# HighPowerWS2801_v1_smd.net
KiCad netlist of a schematic drawn in EAGLE
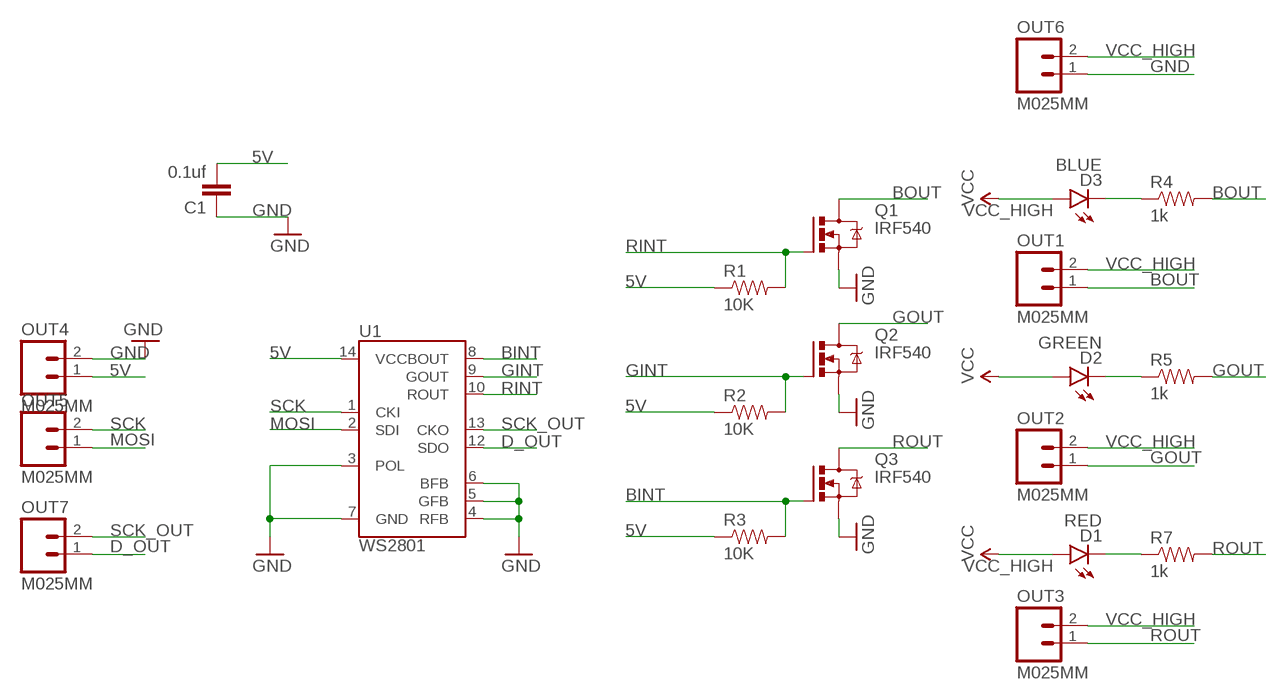
[diagram p0: schematic, sheet 1]

(export (version "E")
  (design (tool "Eeschema 10.0.6"))
  (components
    (comp (ref "C1")
      (value "0.1uf")
      (footprint "eagle-import:0603-CAP")
      (libsource (lib "eagle-import") (part "CAP0603-CAP"))
    )
    (comp (ref "D1")
      (value "RED")
      (footprint "eagle-import:LED-0603")
      (libsource (lib "eagle-import") (part "LED-RED0603"))
    )
    (comp (ref "D2")
      (value "GREEN")
      (footprint "eagle-import:LED-0603")
      (libsource (lib "eagle-import") (part "LED-GREEN0603"))
    )
    (comp (ref "D3")
      (value "BLUE")
      (footprint "eagle-import:LED-0603")
      (libsource (lib "eagle-import") (part "LED-BLUE0603"))
    )
    (comp (ref "OUT1")
      (value "M025MM")
      (footprint "eagle-import:SCREWTERMINAL-5MM-2")
      (libsource (lib "eagle-import") (part "M025MM"))
    )
    (comp (ref "OUT2")
      (value "M025MM")
      (footprint "eagle-import:SCREWTERMINAL-5MM-2")
      (libsource (lib "eagle-import") (part "M025MM"))
    )
    (comp (ref "OUT3")
      (value "M025MM")
      (footprint "eagle-import:SCREWTERMINAL-5MM-2")
      (libsource (lib "eagle-import") (part "M025MM"))
    )
    (comp (ref "OUT4")
      (value "M025MM")
      (footprint "eagle-import:SCREWTERMINAL-5MM-2")
      (libsource (lib "eagle-import") (part "M025MM"))
    )
    (comp (ref "OUT5")
      (value "M025MM")
      (footprint "eagle-import:SCREWTERMINAL-5MM-2")
      (libsource (lib "eagle-import") (part "M025MM"))
    )
    (comp (ref "OUT6")
      (value "M025MM")
      (footprint "eagle-import:SCREWTERMINAL-5MM-2")
      (libsource (lib "eagle-import") (part "M025MM"))
    )
    (comp (ref "OUT7")
      (value "M025MM")
      (footprint "eagle-import:SCREWTERMINAL-5MM-2")
      (libsource (lib "eagle-import") (part "M025MM"))
    )
    (comp (ref "Q1")
      (value "IRF540")
      (footprint "eagle-import:TO220BV")
      (libsource (lib "eagle-import") (part "IRF540"))
    )
    (comp (ref "Q2")
      (value "IRF540")
      (footprint "eagle-import:TO220BV")
      (libsource (lib "eagle-import") (part "IRF540"))
    )
    (comp (ref "Q3")
      (value "IRF540")
      (footprint "eagle-import:TO220BV")
      (libsource (lib "eagle-import") (part "IRF540"))
    )
    (comp (ref "R1")
      (value "10K")
      (footprint "eagle-import:0603-RES")
      (libsource (lib "eagle-import") (part "RESISTOR0603"))
    )
    (comp (ref "R2")
      (value "10K")
      (footprint "eagle-import:0603-RES")
      (libsource (lib "eagle-import") (part "RESISTOR0603"))
    )
    (comp (ref "R3")
      (value "10K")
      (footprint "eagle-import:0603-RES")
      (libsource (lib "eagle-import") (part "RESISTOR0603"))
    )
    (comp (ref "R4")
      (value "1k")
      (footprint "eagle-import:0603-RES")
      (libsource (lib "eagle-import") (part "RESISTOR0603"))
    )
    (comp (ref "R5")
      (value "1k")
      (footprint "eagle-import:0603-RES")
      (libsource (lib "eagle-import") (part "RESISTOR0603"))
    )
    (comp (ref "R7")
      (value "1k")
      (footprint "eagle-import:0603-RES")
      (libsource (lib "eagle-import") (part "RESISTOR0603"))
    )
    (comp (ref "U1")
      (value "WS2801")
      (footprint "eagle-import:SOP-14")
      (libsource (lib "eagle-import") (part "WS2801"))
    )
  )
  (nets
    (net (code "1") (name "/5V") (class "Default")
      (node (ref "C1") (pin "2") (pinfunction "2_2") (pintype "passive"))
      (node (ref "OUT4") (pin "1") (pinfunction "1_1") (pintype "passive"))
      (node (ref "R1") (pin "1") (pinfunction "1_1") (pintype "passive"))
      (node (ref "R2") (pin "1") (pinfunction "1_1") (pintype "passive"))
      (node (ref "R3") (pin "1") (pinfunction "1_1") (pintype "passive"))
      (node (ref "U1") (pin "14") (pinfunction "VCC_14") (pintype "bidirectional"))
    )
    (net (code "2") (name "/BINT") (class "Default")
      (node (ref "Q3") (pin "G") (pinfunction "G_G") (pintype "passive"))
      (node (ref "R3") (pin "2") (pinfunction "2_2") (pintype "passive"))
      (node (ref "U1") (pin "8") (pinfunction "BOUT_8") (pintype "bidirectional"))
    )
    (net (code "3") (name "/BOUT") (class "Default")
      (node (ref "OUT1") (pin "1") (pinfunction "1_1") (pintype "passive"))
      (node (ref "Q1") (pin "D") (pinfunction "D_D") (pintype "passive"))
      (node (ref "R4") (pin "2") (pinfunction "2_2") (pintype "passive"))
    )
    (net (code "4") (name "/D_OUT") (class "Default")
      (node (ref "OUT7") (pin "1") (pinfunction "1_1") (pintype "passive"))
      (node (ref "U1") (pin "12") (pinfunction "SDO_12") (pintype "bidirectional"))
    )
    (net (code "5") (name "/GINT") (class "Default")
      (node (ref "Q2") (pin "G") (pinfunction "G_G") (pintype "passive"))
      (node (ref "R2") (pin "2") (pinfunction "2_2") (pintype "passive"))
      (node (ref "U1") (pin "9") (pinfunction "GOUT_9") (pintype "bidirectional"))
    )
    (net (code "6") (name "/GOUT") (class "Default")
      (node (ref "OUT2") (pin "1") (pinfunction "1_1") (pintype "passive"))
      (node (ref "Q2") (pin "D") (pinfunction "D_D") (pintype "passive"))
      (node (ref "R5") (pin "2") (pinfunction "2_2") (pintype "passive"))
    )
    (net (code "7") (name "/MOSI") (class "Default")
      (node (ref "OUT5") (pin "1") (pinfunction "1_1") (pintype "passive"))
      (node (ref "U1") (pin "2") (pinfunction "SDI_2") (pintype "bidirectional"))
    )
    (net (code "8") (name "/RINT") (class "Default")
      (node (ref "Q1") (pin "G") (pinfunction "G_G") (pintype "passive"))
      (node (ref "R1") (pin "2") (pinfunction "2_2") (pintype "passive"))
      (node (ref "U1") (pin "10") (pinfunction "ROUT_10") (pintype "bidirectional"))
    )
    (net (code "9") (name "/ROUT") (class "Default")
      (node (ref "OUT3") (pin "1") (pinfunction "1_1") (pintype "passive"))
      (node (ref "Q3") (pin "D") (pinfunction "D_D") (pintype "passive"))
      (node (ref "R7") (pin "2") (pinfunction "2_2") (pintype "passive"))
    )
    (net (code "10") (name "/SCK") (class "Default")
      (node (ref "OUT5") (pin "2") (pinfunction "2_2") (pintype "passive"))
      (node (ref "U1") (pin "1") (pinfunction "CKI_1") (pintype "bidirectional"))
    )
    (net (code "11") (name "/SCK_OUT") (class "Default")
      (node (ref "OUT7") (pin "2") (pinfunction "2_2") (pintype "passive"))
      (node (ref "U1") (pin "13") (pinfunction "CKO_13") (pintype "bidirectional"))
    )
    (net (code "12") (name "GND") (class "Default")
      (node (ref "C1") (pin "1") (pinfunction "1_1") (pintype "passive"))
      (node (ref "OUT4") (pin "2") (pinfunction "2_2") (pintype "passive"))
      (node (ref "OUT6") (pin "1") (pinfunction "1_1") (pintype "passive"))
      (node (ref "Q1") (pin "S") (pinfunction "S_S") (pintype "passive"))
      (node (ref "Q2") (pin "S") (pinfunction "S_S") (pintype "passive"))
      (node (ref "Q3") (pin "S") (pinfunction "S_S") (pintype "passive"))
      (node (ref "U1") (pin "3") (pinfunction "POL_3") (pintype "bidirectional"))
      (node (ref "U1") (pin "4") (pinfunction "RFB_4") (pintype "bidirectional"))
      (node (ref "U1") (pin "5") (pinfunction "GFB_5") (pintype "bidirectional"))
      (node (ref "U1") (pin "6") (pinfunction "BFB_6") (pintype "bidirectional"))
      (node (ref "U1") (pin "7") (pinfunction "GND_7") (pintype "bidirectional"))
    )
    (net (code "13") (name "Net-(D1-PadC)") (class "Default")
      (node (ref "D1") (pin "C") (pinfunction "C_C") (pintype "passive"))
      (node (ref "R7") (pin "1") (pinfunction "1_1") (pintype "passive"))
    )
    (net (code "14") (name "Net-(D2-PadC)") (class "Default")
      (node (ref "D2") (pin "C") (pinfunction "C_C") (pintype "passive"))
      (node (ref "R5") (pin "1") (pinfunction "1_1") (pintype "passive"))
    )
    (net (code "15") (name "Net-(D3-PadC)") (class "Default")
      (node (ref "D3") (pin "C") (pinfunction "C_C") (pintype "passive"))
      (node (ref "R4") (pin "1") (pinfunction "1_1") (pintype "passive"))
    )
    (net (code "16") (name "VCC") (class "Default")
      (node (ref "D1") (pin "A") (pinfunction "A_A") (pintype "passive"))
      (node (ref "D2") (pin "A") (pinfunction "A_A") (pintype "passive"))
      (node (ref "D3") (pin "A") (pinfunction "A_A") (pintype "passive"))
      (node (ref "OUT1") (pin "2") (pinfunction "2_2") (pintype "passive"))
      (node (ref "OUT2") (pin "2") (pinfunction "2_2") (pintype "passive"))
      (node (ref "OUT3") (pin "2") (pinfunction "2_2") (pintype "passive"))
      (node (ref "OUT6") (pin "2") (pinfunction "2_2") (pintype "passive"))
    )
  )
)
